# Drawdio_v10.net
KiCad netlist of a schematic drawn in EAGLE
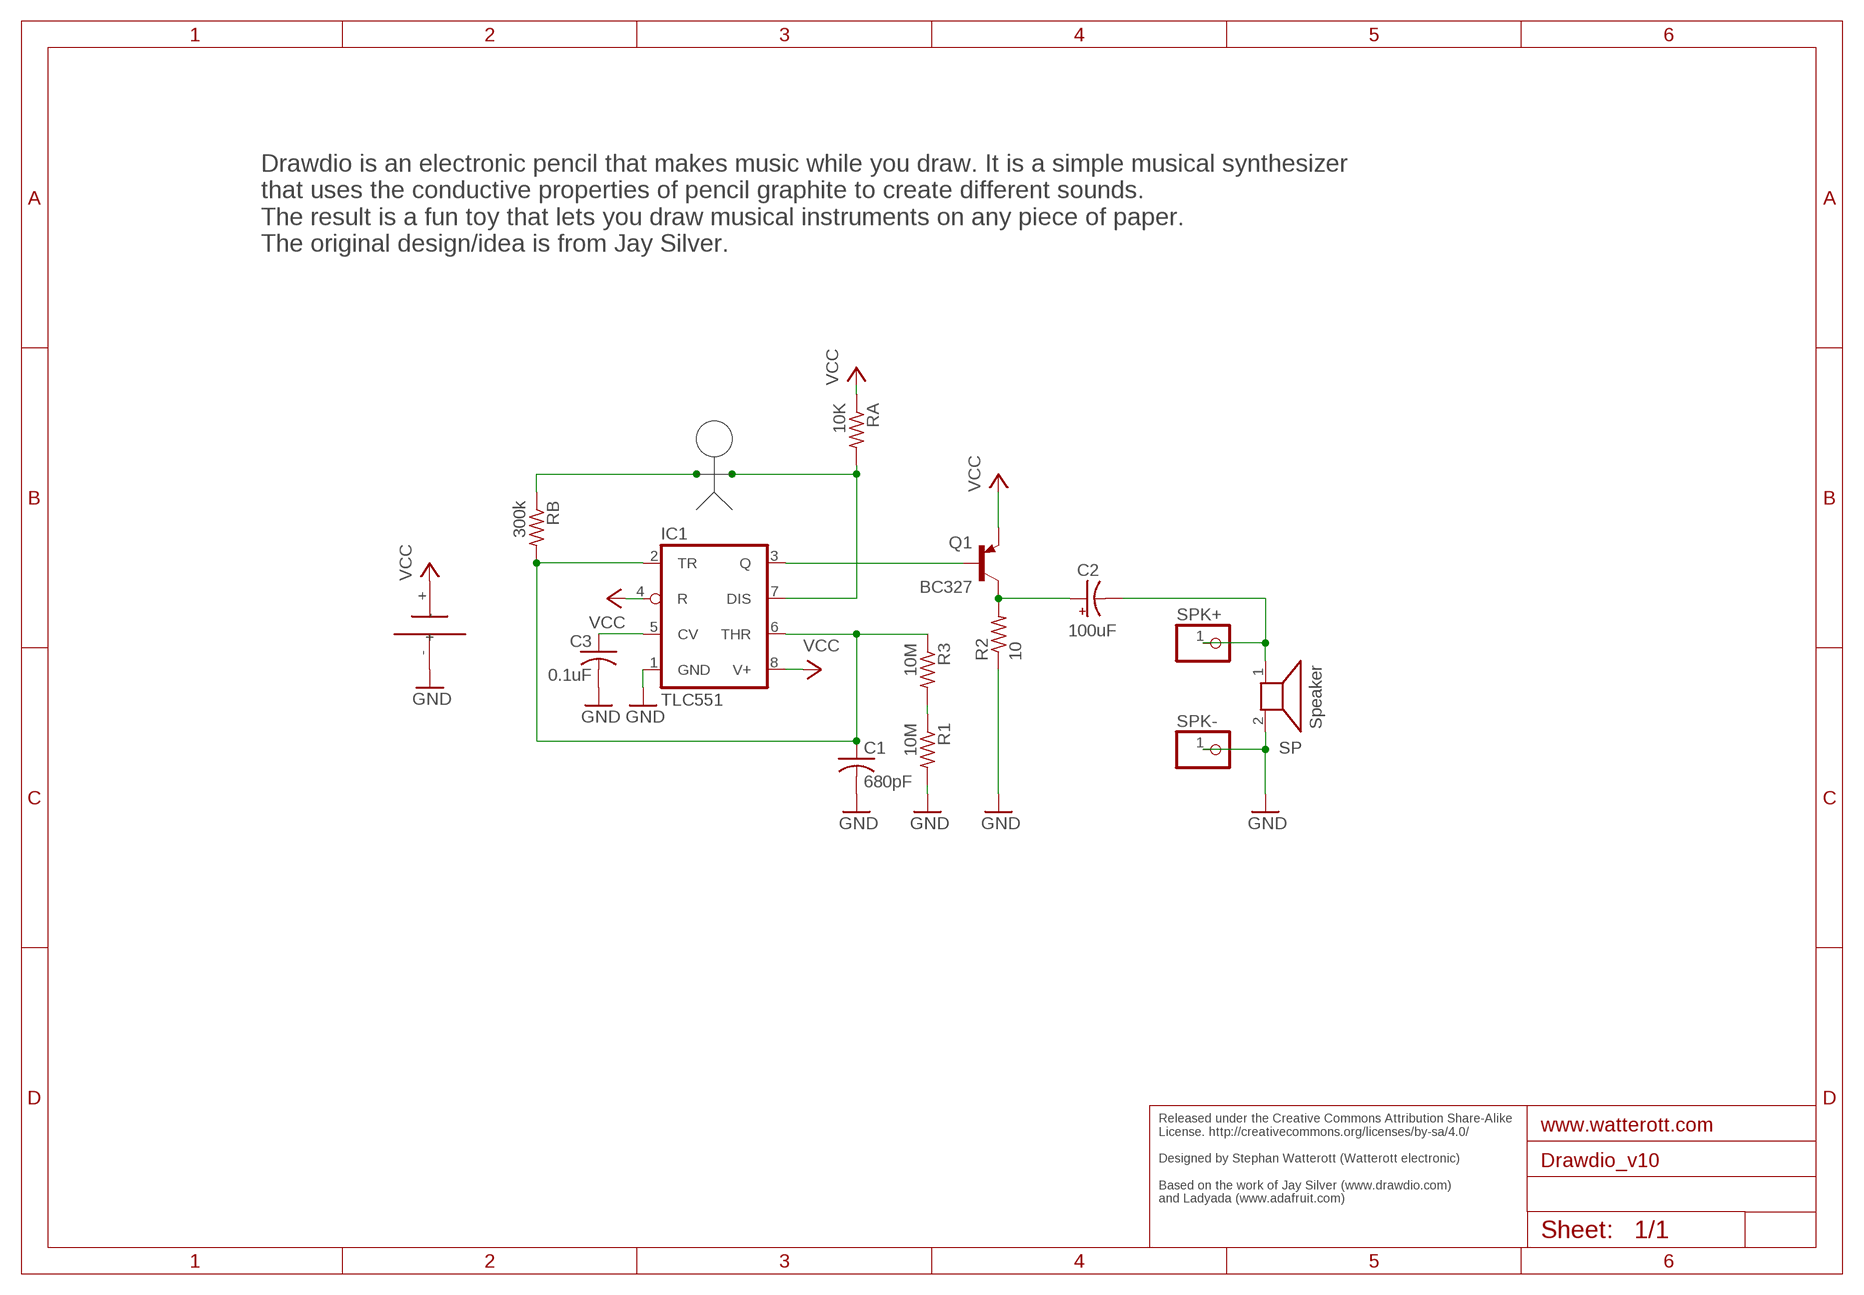
[diagram p0: schematic, sheet 1]

(export (version "E")
  (design (tool "Eeschema 10.0.6"))
  (components
    (comp (ref "C1")
      (value "680pF")
      (footprint "eagle-import:C025-025X050")
      (libsource (lib "eagle-import") (part "C-US025-025X050"))
    )
    (comp (ref "C2")
      (value "100uF")
      (footprint "eagle-import:E2,5-5")
      (libsource (lib "eagle-import") (part "CPOL-USE2.5-5"))
    )
    (comp (ref "C3")
      (value "0.1uF")
      (footprint "eagle-import:C025-025X050")
      (libsource (lib "eagle-import") (part "C-US025-025X050"))
    )
    (comp (ref "IC1")
      (value "TLC551")
      (footprint "eagle-import:DIL08")
      (libsource (lib "eagle-import") (part "555NNE"))
    )
    (comp (ref "Q1")
      (value "BC327")
      (footprint "eagle-import:TO92-CBE")
      (libsource (lib "eagle-import") (part "-PNP-TO92-CBEMPS2907A"))
    )
    (comp (ref "R1")
      (value "10M")
      (footprint "eagle-import:0207_10")
      (libsource (lib "eagle-import") (part "R-US_0207/10"))
    )
    (comp (ref "R2")
      (value "10")
      (footprint "eagle-import:0207_10")
      (libsource (lib "eagle-import") (part "R-US_0207/10"))
    )
    (comp (ref "R3")
      (value "10M")
      (footprint "eagle-import:0207_10")
      (libsource (lib "eagle-import") (part "R-US_0207/10"))
    )
    (comp (ref "RA")
      (value "10K")
      (footprint "eagle-import:0207_10")
      (libsource (lib "eagle-import") (part "R-US_0207/10"))
    )
    (comp (ref "RB")
      (value "300k")
      (footprint "eagle-import:0207_10")
      (libsource (lib "eagle-import") (part "R-US_0207/10"))
    )
    (comp (ref "SP")
      (value "Speaker")
      (footprint "eagle-import:PS603")
      (libsource (lib "eagle-import") (part "PS603SPK"))
    )
    (comp (ref "SPK+")
      (value "PINHD-1X1")
      (footprint "eagle-import:1X01")
      (libsource (lib "eagle-import") (part "PINHD-1X1"))
    )
    (comp (ref "SPK-")
      (value "PINHD-1X1")
      (footprint "eagle-import:1X01")
      (libsource (lib "eagle-import") (part "PINHD-1X1"))
    )
    (comp (ref "U$1")
      (value "AAA")
      (footprint "eagle-import:AAA")
      (libsource (lib "eagle-import") (part "AAA"))
    )
  )
  (nets
    (net (code "1") (name "GND") (class "Default")
      (node (ref "C1") (pin "2") (pinfunction "2_2") (pintype "passive"))
      (node (ref "C3") (pin "2") (pinfunction "2_2") (pintype "passive"))
      (node (ref "IC1") (pin "1") (pinfunction "GND_1") (pintype "power_in"))
      (node (ref "R1") (pin "2") (pinfunction "2_2") (pintype "passive"))
      (node (ref "R2") (pin "1") (pinfunction "1_1") (pintype "passive"))
      (node (ref "SP") (pin "2") (pinfunction "2_2") (pintype "passive"))
      (node (ref "SPK-") (pin "1") (pinfunction "1_1") (pintype "passive"))
      (node (ref "U$1") (pin "-") (pinfunction "-_-") (pintype "bidirectional"))
    )
    (net (code "2") (name "Net-(C2-Pad+)") (class "Default")
      (node (ref "C2") (pin "+") (pinfunction "+_+") (pintype "passive"))
      (node (ref "Q1") (pin "C") (pinfunction "C_C") (pintype "passive"))
      (node (ref "R2") (pin "2") (pinfunction "2_2") (pintype "passive"))
    )
    (net (code "3") (name "Net-(C2-Pad-)") (class "Default")
      (node (ref "C2") (pin "-") (pinfunction "-_-") (pintype "passive"))
      (node (ref "SP") (pin "1") (pinfunction "1_1") (pintype "passive"))
      (node (ref "SPK+") (pin "1") (pinfunction "1_1") (pintype "passive"))
    )
    (net (code "4") (name "Net-(IC1-CV)") (class "Default")
      (node (ref "C3") (pin "1") (pinfunction "1_1") (pintype "passive"))
      (node (ref "IC1") (pin "5") (pinfunction "CV_5") (pintype "input"))
    )
    (net (code "5") (name "Net-(IC1-DIS)") (class "Default")
      (node (ref "IC1") (pin "7") (pinfunction "DIS_7") (pintype "input"))
      (node (ref "RA") (pin "2") (pinfunction "2_2") (pintype "passive"))
    )
    (net (code "6") (name "Net-(IC1-Q)") (class "Default")
      (node (ref "IC1") (pin "3") (pinfunction "Q_3") (pintype "output"))
      (node (ref "Q1") (pin "B") (pinfunction "B_B") (pintype "passive"))
    )
    (net (code "7") (name "Net-(IC1-THR)") (class "Default")
      (node (ref "C1") (pin "1") (pinfunction "1_1") (pintype "passive"))
      (node (ref "IC1") (pin "2") (pinfunction "TR_2") (pintype "input"))
      (node (ref "IC1") (pin "6") (pinfunction "THR_6") (pintype "input"))
      (node (ref "R3") (pin "1") (pinfunction "1_1") (pintype "passive"))
      (node (ref "RB") (pin "2") (pinfunction "2_2") (pintype "passive"))
    )
    (net (code "8") (name "Net-(R1-Pad1)") (class "Default")
      (node (ref "R1") (pin "1") (pinfunction "1_1") (pintype "passive"))
      (node (ref "R3") (pin "2") (pinfunction "2_2") (pintype "passive"))
    )
    (net (code "9") (name "VCC") (class "Default")
      (node (ref "IC1") (pin "4") (pinfunction "R_4") (pintype "input"))
      (node (ref "IC1") (pin "8") (pinfunction "V+_8") (pintype "power_in"))
      (node (ref "Q1") (pin "E") (pinfunction "E_E") (pintype "passive"))
      (node (ref "RA") (pin "1") (pinfunction "1_1") (pintype "passive"))
      (node (ref "U$1") (pin "+") (pinfunction "+_+") (pintype "bidirectional"))
    )
    (net (code "10") (name "unconnected-(RB-Pad1)") (class "Default")
      (node (ref "RB") (pin "1") (pinfunction "1_1") (pintype "passive"))
    )
  )
)
